# accessoryidk.net
KiCad netlist of a schematic drawn in Altium Designer
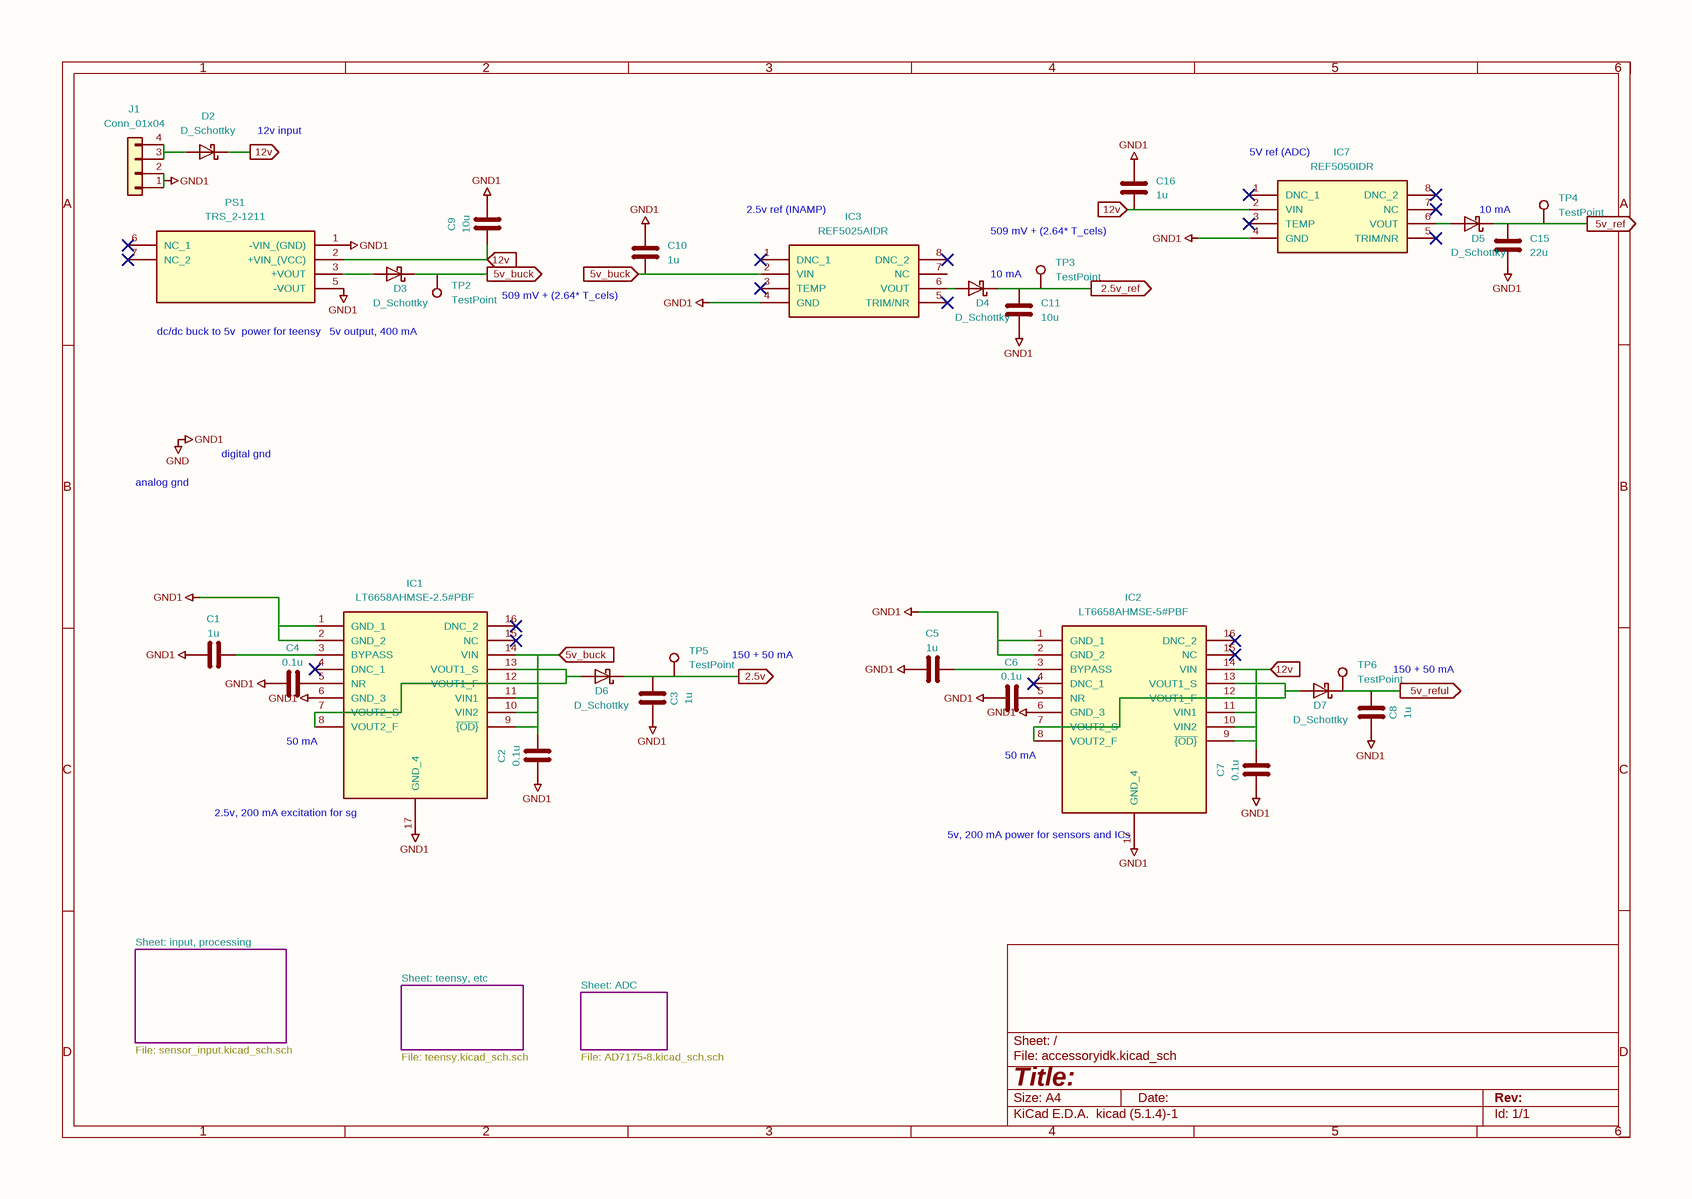
[diagram p0: accessoryidk.SchDoc]

(export (version "E")
  (design (tool "Eeschema 10.0.6"))
  (components
    (comp (ref "C1") (value "1u") (libsource (lib "Device") (part "C")))
    (comp (ref "C2") (value "0.1u") (libsource (lib "Device") (part "C")))
    (comp (ref "C3") (value "1u") (libsource (lib "Device") (part "C")))
    (comp (ref "C4") (value "0.1u") (libsource (lib "Device") (part "C")))
    (comp (ref "C5") (value "1u") (libsource (lib "Device") (part "C")))
    (comp (ref "C6") (value "0.1u") (libsource (lib "Device") (part "C")))
    (comp (ref "C7") (value "0.1u") (libsource (lib "Device") (part "C")))
    (comp (ref "C8") (value "1u") (libsource (lib "Device") (part "C")))
    (comp (ref "C9") (value "10u") (libsource (lib "Device") (part "C")))
    (comp (ref "C10") (value "1u") (libsource (lib "Device") (part "C")))
    (comp (ref "C11") (value "10u") (libsource (lib "Device") (part "C")))
    (comp (ref "C15") (value "22u") (libsource (lib "Device") (part "C")))
    (comp (ref "C16") (value "1u") (libsource (lib "Device") (part "C")))
    (comp (ref "D2") (value "D_Schottky") (libsource (lib "Device") (part "D_Schottky")))
    (comp (ref "D3") (value "D_Schottky") (libsource (lib "Device") (part "D_Schottky")))
    (comp (ref "D4") (value "D_Schottky") (libsource (lib "Device") (part "D_Schottky")))
    (comp (ref "D5") (value "D_Schottky") (libsource (lib "Device") (part "D_Schottky")))
    (comp (ref "D6") (value "D_Schottky") (libsource (lib "Device") (part "D_Schottky")))
    (comp (ref "D7") (value "D_Schottky") (libsource (lib "Device") (part "D_Schottky")))
    (comp (ref "IC1")
      (value "LT6658AHMSE-2.5#PBF")
      (fields (field (name "MOUSER PART NUMBER") "584-LT6658AHMSE5PBF"))
      (libsource (lib "21xt_symbols") (part "LT6658AHMSE-2.5#PBF"))
    )
    (comp (ref "IC2")
      (value "LT6658AHMSE-5#PBF")
      (fields (field (name "MOUSER PART NUMBER") "584-LT6658AHMSE5PBF"))
      (libsource (lib "21xt_symbols") (part "LT6658AHMSE-5#PBF"))
    )
    (comp (ref "IC3")
      (value "REF5025AIDR")
      (fields
        (field (name "MOUSER PART NUMBER") "595-REF5050IDR")
        (field (name "MANUFACTURER_PART_NUMBER") "REF5050IDR")
      )
      (libsource (lib "21xt_symbols") (part "REF5050IDR"))
    )
    (comp (ref "IC7")
      (value "REF5050IDR")
      (fields (field (name "MOUSER PART NUMBER") "595-REF5050IDR"))
      (libsource (lib "21xt_symbols") (part "REF5050IDR"))
    )
    (comp (ref "J1") (value "Conn_01x04") (libsource (lib "Connector_Generic") (part "Conn_01x04")))
    (comp (ref "PS1")
      (value "TRS_2-1211")
      (fields
        (field (name "MOUSER PART NUMBER") "495-TRS2-1211")
        (field (name "MANUFACTURER_PART_NUMBER") "TRS 2-1211")
      )
      (libsource (lib "21xt_symbols") (part "TRS_2-1211"))
    )
    (comp (ref "TP2") (value "TestPoint") (libsource (lib "Connector") (part "TestPoint")))
    (comp (ref "TP3") (value "TestPoint") (libsource (lib "Connector") (part "TestPoint")))
    (comp (ref "TP4") (value "TestPoint") (libsource (lib "Connector") (part "TestPoint")))
    (comp (ref "TP5") (value "TestPoint") (libsource (lib "Connector") (part "TestPoint")))
    (comp (ref "TP6") (value "TestPoint") (libsource (lib "Connector") (part "TestPoint")))
  )
  (nets
    (net (code "1") (name "/2.5v") (class "Default")
      (node (ref "C3") (pin "2") (pinfunction "2_2") (pintype "passive"))
      (node (ref "D6") (pin "1") (pinfunction "K_1") (pintype "passive"))
      (node (ref "TP5") (pin "1") (pinfunction "1_1") (pintype "passive"))
    )
    (net (code "2") (name "/2.5v_ref") (class "Default")
      (node (ref "C11") (pin "1") (pinfunction "1_1") (pintype "passive"))
      (node (ref "D4") (pin "1") (pinfunction "K_1") (pintype "passive"))
      (node (ref "TP3") (pin "1") (pinfunction "1_1") (pintype "passive"))
    )
    (net (code "3") (name "/5v_buck") (class "Default")
      (node (ref "C10") (pin "1") (pinfunction "1_1") (pintype "passive"))
      (node (ref "C2") (pin "2") (pinfunction "2_2") (pintype "passive"))
      (node (ref "D3") (pin "1") (pinfunction "K_1") (pintype "passive"))
      (node (ref "IC1") (pin "10") (pinfunction "VIN2_10") (pintype "passive"))
      (node (ref "IC1") (pin "11") (pinfunction "VIN1_11") (pintype "passive"))
      (node (ref "IC1") (pin "14") (pinfunction "VIN_14") (pintype "passive"))
      (node (ref "IC1") (pin "9") (pinfunction "~{{OD}}_9") (pintype "passive"))
      (node (ref "IC3") (pin "2") (pinfunction "VIN_2") (pintype "passive"))
      (node (ref "TP2") (pin "1") (pinfunction "1_1") (pintype "passive"))
    )
    (net (code "4") (name "/5v_ref") (class "Default")
      (node (ref "C15") (pin "1") (pinfunction "1_1") (pintype "passive"))
      (node (ref "D5") (pin "1") (pinfunction "K_1") (pintype "passive"))
      (node (ref "TP4") (pin "1") (pinfunction "1_1") (pintype "passive"))
    )
    (net (code "5") (name "/5v_reful") (class "Default")
      (node (ref "C8") (pin "2") (pinfunction "2_2") (pintype "passive"))
      (node (ref "D7") (pin "1") (pinfunction "K_1") (pintype "passive"))
      (node (ref "TP6") (pin "1") (pinfunction "1_1") (pintype "passive"))
    )
    (net (code "6") (name "/12v") (class "Default")
      (node (ref "C16") (pin "1") (pinfunction "1_1") (pintype "passive"))
      (node (ref "C7") (pin "2") (pinfunction "2_2") (pintype "passive"))
      (node (ref "C9") (pin "1") (pinfunction "1_1") (pintype "passive"))
      (node (ref "D2") (pin "1") (pinfunction "K_1") (pintype "passive"))
      (node (ref "IC2") (pin "10") (pinfunction "VIN2_10") (pintype "passive"))
      (node (ref "IC2") (pin "11") (pinfunction "VIN1_11") (pintype "passive"))
      (node (ref "IC2") (pin "14") (pinfunction "VIN_14") (pintype "passive"))
      (node (ref "IC2") (pin "9") (pinfunction "~{{OD}}_9") (pintype "passive"))
      (node (ref "IC7") (pin "2") (pinfunction "VIN_2") (pintype "passive"))
      (node (ref "PS1") (pin "2") (pinfunction "+VIN_(VCC)_2") (pintype "passive"))
    )
    (net (code "7") (name "GND") (class "Default")
      (node (ref "C1") (pin "1") (pinfunction "1_1") (pintype "passive"))
      (node (ref "C10") (pin "2") (pinfunction "2_2") (pintype "passive"))
      (node (ref "C11") (pin "2") (pinfunction "2_2") (pintype "passive"))
      (node (ref "C15") (pin "2") (pinfunction "2_2") (pintype "passive"))
      (node (ref "C16") (pin "2") (pinfunction "2_2") (pintype "passive"))
      (node (ref "C2") (pin "1") (pinfunction "1_1") (pintype "passive"))
      (node (ref "C3") (pin "1") (pinfunction "1_1") (pintype "passive"))
      (node (ref "C4") (pin "1") (pinfunction "1_1") (pintype "passive"))
      (node (ref "C5") (pin "1") (pinfunction "1_1") (pintype "passive"))
      (node (ref "C6") (pin "1") (pinfunction "1_1") (pintype "passive"))
      (node (ref "C7") (pin "1") (pinfunction "1_1") (pintype "passive"))
      (node (ref "C8") (pin "1") (pinfunction "1_1") (pintype "passive"))
      (node (ref "C9") (pin "2") (pinfunction "2_2") (pintype "passive"))
      (node (ref "IC1") (pin "1") (pinfunction "GND_1_1") (pintype "passive"))
      (node (ref "IC1") (pin "17") (pinfunction "GND_4_17") (pintype "passive"))
      (node (ref "IC1") (pin "2") (pinfunction "GND_2_2") (pintype "passive"))
      (node (ref "IC1") (pin "6") (pinfunction "GND_3_6") (pintype "passive"))
      (node (ref "IC2") (pin "1") (pinfunction "GND_1_1") (pintype "passive"))
      (node (ref "IC2") (pin "17") (pinfunction "GND_4_17") (pintype "passive"))
      (node (ref "IC2") (pin "2") (pinfunction "GND_2_2") (pintype "passive"))
      (node (ref "IC2") (pin "6") (pinfunction "GND_3_6") (pintype "passive"))
      (node (ref "IC3") (pin "4") (pinfunction "GND_4") (pintype "passive"))
      (node (ref "IC7") (pin "4") (pinfunction "GND_4") (pintype "passive"))
      (node (ref "J1") (pin "1") (pinfunction "Pin_1_1") (pintype "passive"))
      (node (ref "J1") (pin "2") (pinfunction "Pin_2_2") (pintype "passive"))
      (node (ref "PS1") (pin "1") (pinfunction "-VIN_(GND)_1") (pintype "passive"))
      (node (ref "PS1") (pin "5") (pinfunction "-VOUT_5") (pintype "passive"))
    )
    (net (code "8") (name "Net-(D2-A)") (class "Default")
      (node (ref "D2") (pin "2") (pinfunction "A_2") (pintype "passive"))
      (node (ref "J1") (pin "3") (pinfunction "Pin_3_3") (pintype "passive"))
      (node (ref "J1") (pin "4") (pinfunction "Pin_4_4") (pintype "passive"))
    )
    (net (code "9") (name "Net-(D3-A)") (class "Default")
      (node (ref "D3") (pin "2") (pinfunction "A_2") (pintype "passive"))
      (node (ref "PS1") (pin "3") (pinfunction "+VOUT_3") (pintype "passive"))
    )
    (net (code "10") (name "Net-(D4-A)") (class "Default")
      (node (ref "D4") (pin "2") (pinfunction "A_2") (pintype "passive"))
      (node (ref "IC3") (pin "6") (pinfunction "VOUT_6") (pintype "passive"))
    )
    (net (code "11") (name "Net-(D5-A)") (class "Default")
      (node (ref "D5") (pin "2") (pinfunction "A_2") (pintype "passive"))
      (node (ref "IC7") (pin "6") (pinfunction "VOUT_6") (pintype "passive"))
    )
    (net (code "12") (name "Net-(D6-A)") (class "Default")
      (node (ref "D6") (pin "2") (pinfunction "A_2") (pintype "passive"))
      (node (ref "IC1") (pin "12") (pinfunction "VOUT1_F_12") (pintype "passive"))
      (node (ref "IC1") (pin "13") (pinfunction "VOUT1_S_13") (pintype "passive"))
      (node (ref "IC1") (pin "7") (pinfunction "VOUT2_S_7") (pintype "passive"))
      (node (ref "IC1") (pin "8") (pinfunction "VOUT2_F_8") (pintype "passive"))
    )
    (net (code "13") (name "Net-(D7-A)") (class "Default")
      (node (ref "D7") (pin "2") (pinfunction "A_2") (pintype "passive"))
      (node (ref "IC2") (pin "12") (pinfunction "VOUT1_F_12") (pintype "passive"))
      (node (ref "IC2") (pin "13") (pinfunction "VOUT1_S_13") (pintype "passive"))
      (node (ref "IC2") (pin "7") (pinfunction "VOUT2_S_7") (pintype "passive"))
      (node (ref "IC2") (pin "8") (pinfunction "VOUT2_F_8") (pintype "passive"))
    )
    (net (code "14") (name "Net-(IC1-BYPASS)") (class "Default")
      (node (ref "C1") (pin "2") (pinfunction "2_2") (pintype "passive"))
      (node (ref "IC1") (pin "3") (pinfunction "BYPASS_3") (pintype "passive"))
    )
    (net (code "15") (name "Net-(IC1-NR)") (class "Default")
      (node (ref "C4") (pin "2") (pinfunction "2_2") (pintype "passive"))
      (node (ref "IC1") (pin "5") (pinfunction "NR_5") (pintype "passive"))
    )
    (net (code "16") (name "Net-(IC2-BYPASS)") (class "Default")
      (node (ref "C5") (pin "2") (pinfunction "2_2") (pintype "passive"))
      (node (ref "IC2") (pin "3") (pinfunction "BYPASS_3") (pintype "passive"))
    )
    (net (code "17") (name "Net-(IC2-NR)") (class "Default")
      (node (ref "C6") (pin "2") (pinfunction "2_2") (pintype "passive"))
      (node (ref "IC2") (pin "5") (pinfunction "NR_5") (pintype "passive"))
    )
    (net (code "18") (name "unconnected-(IC1-DNC_1-Pad4)") (class "Default")
      (node (ref "IC1") (pin "4") (pinfunction "DNC_1_4") (pintype "passive+no_connect"))
    )
    (net (code "19") (name "unconnected-(IC1-DNC_2-Pad16)") (class "Default")
      (node (ref "IC1") (pin "16") (pinfunction "DNC_2_16") (pintype "passive+no_connect"))
    )
    (net (code "20") (name "unconnected-(IC1-NC-Pad15)") (class "Default")
      (node (ref "IC1") (pin "15") (pinfunction "NC_15") (pintype "passive+no_connect"))
    )
    (net (code "21") (name "unconnected-(IC2-DNC_1-Pad4)") (class "Default")
      (node (ref "IC2") (pin "4") (pinfunction "DNC_1_4") (pintype "passive+no_connect"))
    )
    (net (code "22") (name "unconnected-(IC2-DNC_2-Pad16)") (class "Default")
      (node (ref "IC2") (pin "16") (pinfunction "DNC_2_16") (pintype "passive+no_connect"))
    )
    (net (code "23") (name "unconnected-(IC2-NC-Pad15)") (class "Default")
      (node (ref "IC2") (pin "15") (pinfunction "NC_15") (pintype "passive+no_connect"))
    )
    (net (code "24") (name "unconnected-(IC3-DNC_1-Pad1)") (class "Default")
      (node (ref "IC3") (pin "1") (pinfunction "DNC_1_1") (pintype "passive+no_connect"))
    )
    (net (code "25") (name "unconnected-(IC3-DNC_2-Pad8)") (class "Default")
      (node (ref "IC3") (pin "8") (pinfunction "DNC_2_8") (pintype "passive+no_connect"))
    )
    (net (code "26") (name "unconnected-(IC3-NC-Pad7)") (class "Default")
      (node (ref "IC3") (pin "7") (pinfunction "NC_7") (pintype "passive"))
    )
    (net (code "27") (name "unconnected-(IC3-TEMP-Pad3)") (class "Default")
      (node (ref "IC3") (pin "3") (pinfunction "TEMP_3") (pintype "passive+no_connect"))
    )
    (net (code "28") (name "unconnected-(IC3-TRIM{slash}NR-Pad5)") (class "Default")
      (node (ref "IC3") (pin "5") (pinfunction "TRIM/NR_5") (pintype "passive+no_connect"))
    )
    (net (code "29") (name "unconnected-(IC7-DNC_1-Pad1)") (class "Default")
      (node (ref "IC7") (pin "1") (pinfunction "DNC_1_1") (pintype "passive+no_connect"))
    )
    (net (code "30") (name "unconnected-(IC7-DNC_2-Pad8)") (class "Default")
      (node (ref "IC7") (pin "8") (pinfunction "DNC_2_8") (pintype "passive+no_connect"))
    )
    (net (code "31") (name "unconnected-(IC7-NC-Pad7)") (class "Default")
      (node (ref "IC7") (pin "7") (pinfunction "NC_7") (pintype "passive+no_connect"))
    )
    (net (code "32") (name "unconnected-(IC7-TEMP-Pad3)") (class "Default")
      (node (ref "IC7") (pin "3") (pinfunction "TEMP_3") (pintype "passive+no_connect"))
    )
    (net (code "33") (name "unconnected-(IC7-TRIM{slash}NR-Pad5)") (class "Default")
      (node (ref "IC7") (pin "5") (pinfunction "TRIM/NR_5") (pintype "passive+no_connect"))
    )
    (net (code "34") (name "unconnected-(PS1-NC_1-Pad6)") (class "Default")
      (node (ref "PS1") (pin "6") (pinfunction "NC_1_6") (pintype "passive+no_connect"))
    )
    (net (code "35") (name "unconnected-(PS1-NC_2-Pad7)") (class "Default")
      (node (ref "PS1") (pin "7") (pinfunction "NC_2_7") (pintype "passive+no_connect"))
    )
  )
)
